# PCB_tp1.net
KiCad netlist of a schematic drawn in Altium Designer
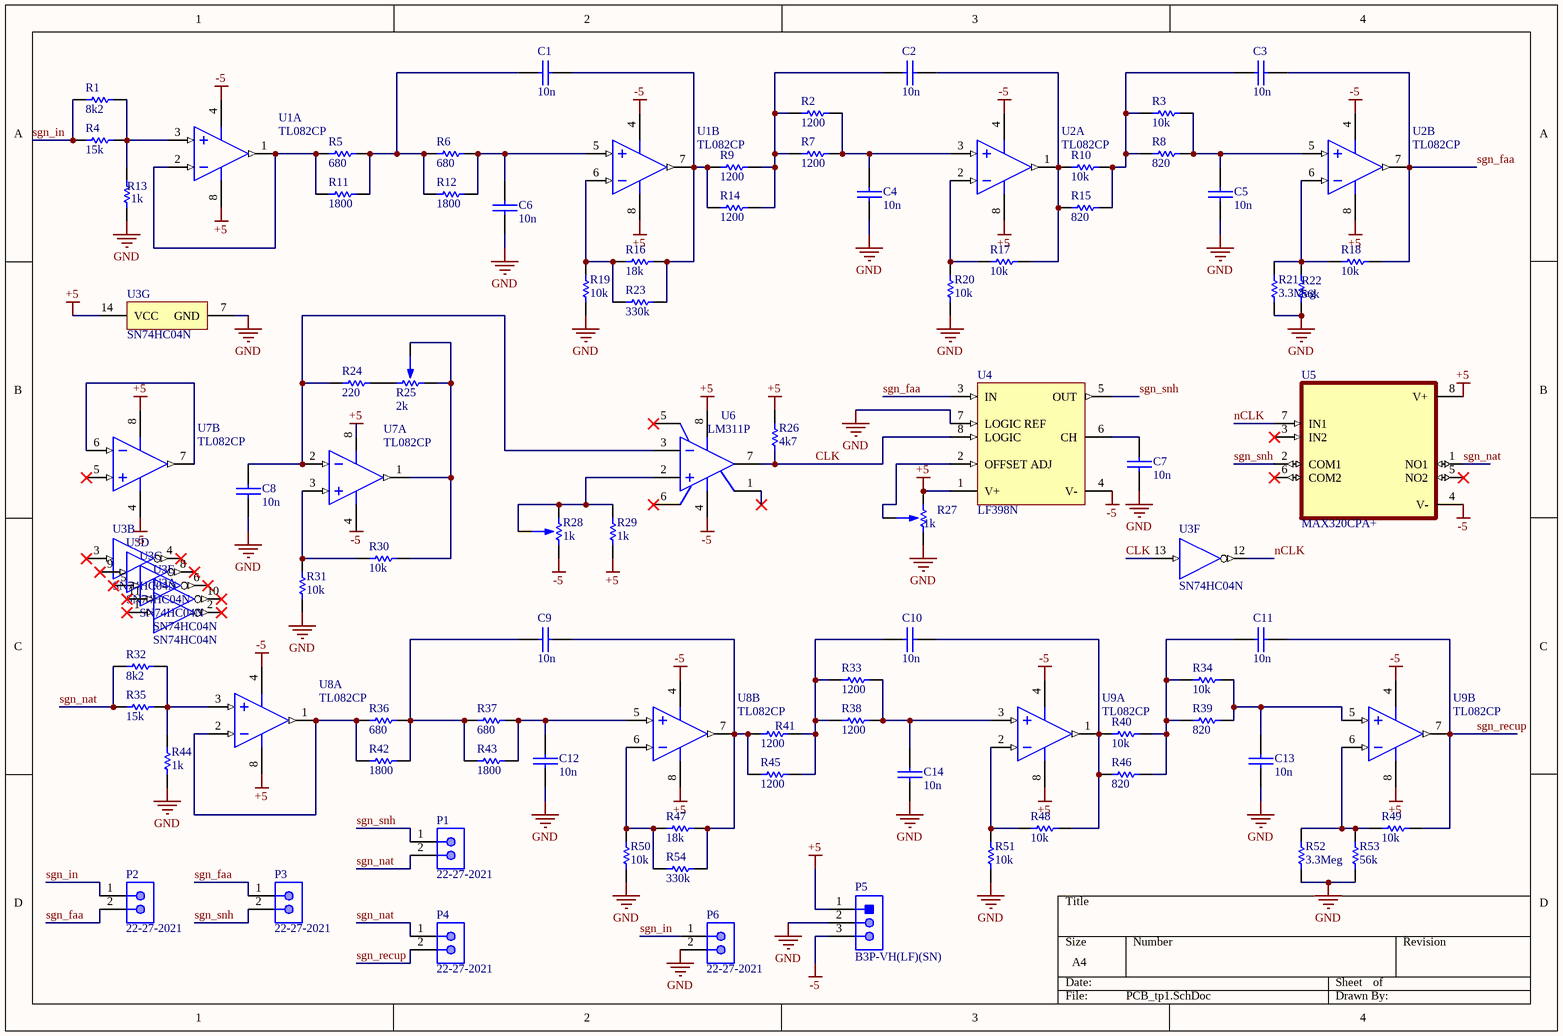
[diagram p0: PCB_tp1.SchDoc]

(export (version "E")
  (design (tool "Eeschema 10.0.6"))
  (components
    (comp (ref "C1") (value "10n") (footprint "CAP200") (libsource (lib "LIBEBAL") (part "CAP")))
    (comp (ref "C2") (value "10n") (footprint "CAP200") (libsource (lib "LIBEBAL") (part "CAP")))
    (comp (ref "C3") (value "10n") (footprint "CAP200") (libsource (lib "LIBEBAL") (part "CAP")))
    (comp (ref "C4") (value "10n") (footprint "CAP200") (libsource (lib "LIBEBAL") (part "CAP")))
    (comp (ref "C5") (value "10n") (footprint "CAP200") (libsource (lib "LIBEBAL") (part "CAP")))
    (comp (ref "C6") (value "10n") (footprint "CAP200") (libsource (lib "LIBEBAL") (part "CAP")))
    (comp (ref "C7") (value "10n") (footprint "CAP200") (libsource (lib "LIBEBAL") (part "CAP")))
    (comp (ref "C8") (value "10n") (footprint "CAP200") (libsource (lib "LIBEBAL") (part "CAP")))
    (comp (ref "C9") (value "10n") (footprint "CAP200") (libsource (lib "LIBEBAL") (part "CAP")))
    (comp (ref "C10") (value "10n") (footprint "CAP200") (libsource (lib "LIBEBAL") (part "CAP")))
    (comp (ref "C11") (value "10n") (footprint "CAP200") (libsource (lib "LIBEBAL") (part "CAP")))
    (comp (ref "C12") (value "10n") (footprint "CAP200") (libsource (lib "LIBEBAL") (part "CAP")))
    (comp (ref "C13") (value "10n") (footprint "CAP200") (libsource (lib "LIBEBAL") (part "CAP")))
    (comp (ref "C14") (value "10n") (footprint "CAP200") (libsource (lib "LIBEBAL") (part "CAP")))
    (comp (ref "P1")
      (value "22-27-2021")
      (footprint "MOLX-22-27-2021_V")
      (fields (field (name "MANUFACTURER") "Molex") (field (name "PARTNUMBER") "0022272021"))
      (libsource (lib "Altium Content Vault") (part "CN-1P-M-R2"))
    )
    (comp (ref "P2")
      (value "22-27-2021")
      (footprint "MOLX-22-27-2021_V")
      (fields (field (name "MANUFACTURER") "Molex") (field (name "PARTNUMBER") "0022272021"))
      (libsource (lib "Altium Content Vault") (part "CN-1P-M-R2"))
    )
    (comp (ref "P3")
      (value "22-27-2021")
      (footprint "MOLX-22-27-2021_V")
      (fields (field (name "MANUFACTURER") "Molex") (field (name "PARTNUMBER") "0022272021"))
      (libsource (lib "Altium Content Vault") (part "CN-1P-M-R2"))
    )
    (comp (ref "P4")
      (value "22-27-2021")
      (footprint "MOLX-22-27-2021_V")
      (fields (field (name "MANUFACTURER") "Molex") (field (name "PARTNUMBER") "0022272021"))
      (libsource (lib "Altium Content Vault") (part "CN-1P-M-R2"))
    )
    (comp (ref "P5")
      (value "B3P-VH(LF)(SN)")
      (footprint "JST-B3P-VH(LF)(SN)-3_V")
      (libsource (lib "Altium Content Vault") (part "CN-1P-M-R3"))
    )
    (comp (ref "P6")
      (value "22-27-2021")
      (footprint "MOLX-22-27-2021_V")
      (fields (field (name "MANUFACTURER") "Molex") (field (name "PARTNUMBER") "0022272021"))
      (libsource (lib "Altium Content Vault") (part "CN-1P-M-R2"))
    )
    (comp (ref "R1") (value "8k2") (footprint "RES400") (libsource (lib "LIBEBAL") (part "RES")))
    (comp (ref "R2") (value "1200") (footprint "RES400") (libsource (lib "LIBEBAL") (part "RES")))
    (comp (ref "R3") (value "10k") (footprint "RES400") (libsource (lib "LIBEBAL") (part "RES")))
    (comp (ref "R4") (value "15k") (footprint "RES400") (libsource (lib "LIBEBAL") (part "RES")))
    (comp (ref "R5") (value "680") (footprint "RES400") (libsource (lib "LIBEBAL") (part "RES")))
    (comp (ref "R6") (value "680") (footprint "RES400") (libsource (lib "LIBEBAL") (part "RES")))
    (comp (ref "R7") (value "1200") (footprint "RES400") (libsource (lib "LIBEBAL") (part "RES")))
    (comp (ref "R8") (value "820") (footprint "RES400") (libsource (lib "LIBEBAL") (part "RES")))
    (comp (ref "R9") (value "1200") (footprint "RES400") (libsource (lib "LIBEBAL") (part "RES")))
    (comp (ref "R10") (value "10k") (footprint "RES400") (libsource (lib "LIBEBAL") (part "RES")))
    (comp (ref "R11") (value "1800") (footprint "RES400") (libsource (lib "LIBEBAL") (part "RES")))
    (comp (ref "R12") (value "1800") (footprint "RES400") (libsource (lib "LIBEBAL") (part "RES")))
    (comp (ref "R13") (value "1k") (footprint "RES400") (libsource (lib "LIBEBAL") (part "RES")))
    (comp (ref "R14") (value "1200") (footprint "RES400") (libsource (lib "LIBEBAL") (part "RES")))
    (comp (ref "R15") (value "820") (footprint "RES400") (libsource (lib "LIBEBAL") (part "RES")))
    (comp (ref "R16") (value "18k") (footprint "RES400") (libsource (lib "LIBEBAL") (part "RES")))
    (comp (ref "R17") (value "10k") (footprint "RES400") (libsource (lib "LIBEBAL") (part "RES")))
    (comp (ref "R18") (value "10k") (footprint "RES400") (libsource (lib "LIBEBAL") (part "RES")))
    (comp (ref "R19") (value "10k") (footprint "RES400") (libsource (lib "LIBEBAL") (part "RES")))
    (comp (ref "R20") (value "10k") (footprint "RES400") (libsource (lib "LIBEBAL") (part "RES")))
    (comp (ref "R21") (value "3.3Meg") (footprint "RES400") (libsource (lib "LIBEBAL") (part "RES")))
    (comp (ref "R22") (value "56k") (footprint "RES400") (libsource (lib "LIBEBAL") (part "RES")))
    (comp (ref "R23") (value "330k") (footprint "RES400") (libsource (lib "LIBEBAL") (part "RES")))
    (comp (ref "R24") (value "220") (footprint "RES400") (libsource (lib "LIBEBAL") (part "RES")))
    (comp (ref "R25")
      (value "2k")
      (footprint "POTENCIOMETRO")
      (libsource (lib "LIBEBAL") (part "POTENCIOMETRO"))
    )
    (comp (ref "R26") (value "4k7") (footprint "RES400") (libsource (lib "LIBEBAL") (part "RES")))
    (comp (ref "R27") (value "1k") (footprint "PRESET H") (libsource (lib "LIBEBAL") (part "PRESET")))
    (comp (ref "R28")
      (value "1k")
      (footprint "POTENCIOMETRO")
      (libsource (lib "LIBEBAL") (part "POTENCIOMETRO"))
    )
    (comp (ref "R29") (value "1k") (footprint "RES400") (libsource (lib "LIBEBAL") (part "RES")))
    (comp (ref "R30") (value "10k") (footprint "RES400") (libsource (lib "LIBEBAL") (part "RES")))
    (comp (ref "R31") (value "10k") (footprint "RES400") (libsource (lib "LIBEBAL") (part "RES")))
    (comp (ref "R32") (value "8k2") (footprint "RES400") (libsource (lib "LIBEBAL") (part "RES")))
    (comp (ref "R33") (value "1200") (footprint "RES400") (libsource (lib "LIBEBAL") (part "RES")))
    (comp (ref "R34") (value "10k") (footprint "RES400") (libsource (lib "LIBEBAL") (part "RES")))
    (comp (ref "R35") (value "15k") (footprint "RES400") (libsource (lib "LIBEBAL") (part "RES")))
    (comp (ref "R36") (value "680") (footprint "RES400") (libsource (lib "LIBEBAL") (part "RES")))
    (comp (ref "R37") (value "680") (footprint "RES400") (libsource (lib "LIBEBAL") (part "RES")))
    (comp (ref "R38") (value "1200") (footprint "RES400") (libsource (lib "LIBEBAL") (part "RES")))
    (comp (ref "R39") (value "820") (footprint "RES400") (libsource (lib "LIBEBAL") (part "RES")))
    (comp (ref "R40") (value "10k") (footprint "RES400") (libsource (lib "LIBEBAL") (part "RES")))
    (comp (ref "R41") (value "1200") (footprint "RES400") (libsource (lib "LIBEBAL") (part "RES")))
    (comp (ref "R42") (value "1800") (footprint "RES400") (libsource (lib "LIBEBAL") (part "RES")))
    (comp (ref "R43") (value "1800") (footprint "RES400") (libsource (lib "LIBEBAL") (part "RES")))
    (comp (ref "R44") (value "1k") (footprint "RES400") (libsource (lib "LIBEBAL") (part "RES")))
    (comp (ref "R45") (value "1200") (footprint "RES400") (libsource (lib "LIBEBAL") (part "RES")))
    (comp (ref "R46") (value "820") (footprint "RES400") (libsource (lib "LIBEBAL") (part "RES")))
    (comp (ref "R47") (value "18k") (footprint "RES400") (libsource (lib "LIBEBAL") (part "RES")))
    (comp (ref "R48") (value "10k") (footprint "RES400") (libsource (lib "LIBEBAL") (part "RES")))
    (comp (ref "R49") (value "10k") (footprint "RES400") (libsource (lib "LIBEBAL") (part "RES")))
    (comp (ref "R50") (value "10k") (footprint "RES400") (libsource (lib "LIBEBAL") (part "RES")))
    (comp (ref "R51") (value "10k") (footprint "RES400") (libsource (lib "LIBEBAL") (part "RES")))
    (comp (ref "R52") (value "3.3Meg") (footprint "RES400") (libsource (lib "LIBEBAL") (part "RES")))
    (comp (ref "R53") (value "56k") (footprint "RES400") (libsource (lib "LIBEBAL") (part "RES")))
    (comp (ref "R54") (value "330k") (footprint "RES400") (libsource (lib "LIBEBAL") (part "RES")))
    (comp (ref "U1")
      (value "TL082CP")
      (footprint "P0008A")
      (description "JFET-Input Operational Amplifier, 7 to 36 V, 0 to 70 degC, 8-pin DIP (P8), Pb-Free (RoHS)")
      (fields (field (name "MANUFACTURER") "Texas Instruments"))
      (libsource (lib "Altium Content Vault") (part "TI-AMP-D6-2-8_D"))
    )
    (comp (ref "U2")
      (value "TL082CP")
      (footprint "P0008A")
      (description "JFET-Input Operational Amplifier, 7 to 36 V, 0 to 70 degC, 8-pin DIP (P8), Pb-Free (RoHS)")
      (fields (field (name "MANUFACTURER") "Texas Instruments"))
      (libsource (lib "Altium Content Vault") (part "TI-AMP-D6-2-8_D"))
    )
    (comp (ref "U3")
      (value "SN74HC04N")
      (footprint "N0014A")
      (description "Hex Inverters, N0014A, TUBE")
      (fields
        (field (name "MANUFACTURER") "Texas Instruments")
        (field (name "GENERIC PART NUMBER") "SN74HC04")
      )
      (libsource (lib "Altium Content Vault") (part "TI-CD_SNX4XXXXXX4X_19A-14"))
    )
    (comp (ref "U4")
      (value "LF398N")
      (footprint "N08E")
      (description "Monolithic Sample and Hold Circuits, 8-pin MDIP")
      (fields (field (name "MANUFACTURER") "National Semiconductor"))
      (libsource (lib "Altium Content Vault") (part "AMP-SHA-LFX98-8"))
    )
    (comp (ref "U5")
      (value "MAX320CPA+")
      (footprint "DIP794W47P254L991H457Q8")
      (description "Precision, Dual Supply, SPST, Analog CMOS Switches")
      (fields (field (name "MF") "Analog Devices"))
      (libsource (lib "MAX320CPA_") (part "MAX320CPA+"))
    )
    (comp (ref "U6")
      (value "LM311P")
      (footprint "FP-P0008A-MFG")
      (fields (field (name "TOLERANCE") "1%"))
      (libsource (lib "Altium Content Vault") (part "b2b1c66385073ed7f685b7e01cc60c1"))
    )
    (comp (ref "U7")
      (value "TL082CP")
      (footprint "P0008A")
      (description "JFET-Input Operational Amplifier, 7 to 36 V, 0 to 70 degC, 8-pin DIP (P8), Pb-Free (RoHS)")
      (fields (field (name "MANUFACTURER") "Texas Instruments"))
      (libsource (lib "Altium Content Vault") (part "TI-AMP-D6-2-8_D"))
    )
    (comp (ref "U8")
      (value "TL082CP")
      (footprint "P0008A")
      (description "JFET-Input Operational Amplifier, 7 to 36 V, 0 to 70 degC, 8-pin DIP (P8), Pb-Free (RoHS)")
      (fields (field (name "MANUFACTURER") "Texas Instruments"))
      (libsource (lib "Altium Content Vault") (part "TI-AMP-D6-2-8_D"))
    )
    (comp (ref "U9")
      (value "TL082CP")
      (footprint "P0008A")
      (description "JFET-Input Operational Amplifier, 7 to 36 V, 0 to 70 degC, 8-pin DIP (P8), Pb-Free (RoHS)")
      (fields (field (name "MANUFACTURER") "Texas Instruments"))
      (libsource (lib "Altium Content Vault") (part "TI-AMP-D6-2-8_D"))
    )
  )
  (nets
    (net (code "1") (name "+5") (class "Default")
      (node (ref "P5") (pin "1") (pinfunction "1_1") (pintype "passive"))
      (node (ref "R26") (pin "1") (pinfunction "1_1") (pintype "passive"))
      (node (ref "R27") (pin "3") (pinfunction "3_3") (pintype "passive"))
      (node (ref "R29") (pin "2") (pinfunction "2_2") (pintype "passive"))
      (node (ref "U1") (pin "8") (pinfunction "VCC+_8") (pintype "power_in"))
      (node (ref "U2") (pin "8") (pinfunction "VCC+_8") (pintype "power_in"))
      (node (ref "U3") (pin "14") (pinfunction "VCC_14") (pintype "power_in"))
      (node (ref "U4") (pin "1") (pinfunction "V+_1") (pintype "power_in"))
      (node (ref "U5") (pin "8") (pinfunction "V+_8") (pintype "power_in"))
      (node (ref "U6") (pin "8") (pinfunction "VCC+_8") (pintype "power_in"))
      (node (ref "U7") (pin "8") (pinfunction "VCC+_8") (pintype "power_in"))
      (node (ref "U8") (pin "8") (pinfunction "VCC+_8") (pintype "power_in"))
      (node (ref "U9") (pin "8") (pinfunction "VCC+_8") (pintype "power_in"))
    )
    (net (code "2") (name "-5") (class "Default")
      (node (ref "P5") (pin "3") (pinfunction "3_3") (pintype "passive"))
      (node (ref "R28") (pin "1") (pinfunction "1_1") (pintype "passive"))
      (node (ref "U1") (pin "4") (pinfunction "VCC-_4") (pintype "power_in"))
      (node (ref "U2") (pin "4") (pinfunction "VCC-_4") (pintype "power_in"))
      (node (ref "U4") (pin "4") (pinfunction "V-_4") (pintype "power_in"))
      (node (ref "U5") (pin "4") (pinfunction "V-_4") (pintype "power_in"))
      (node (ref "U6") (pin "4") (pinfunction "VCC-_4") (pintype "power_in"))
      (node (ref "U7") (pin "4") (pinfunction "VCC-_4") (pintype "power_in"))
      (node (ref "U8") (pin "4") (pinfunction "VCC-_4") (pintype "power_in"))
      (node (ref "U9") (pin "4") (pinfunction "VCC-_4") (pintype "power_in"))
    )
    (net (code "3") (name "/CLK") (class "Default")
      (node (ref "R26") (pin "2") (pinfunction "2_2") (pintype "passive"))
      (node (ref "U3") (pin "13") (pinfunction "6A_13") (pintype "input"))
      (node (ref "U4") (pin "8") (pinfunction "LOGIC_8") (pintype "input"))
      (node (ref "U6") (pin "7") (pinfunction "COL_OUT_7") (pintype "open_collector"))
    )
    (net (code "4") (name "/nCLK") (class "Default")
      (node (ref "U3") (pin "12") (pinfunction "~{6Y}_12") (pintype "output"))
      (node (ref "U5") (pin "7") (pinfunction "IN1_7") (pintype "input"))
    )
    (net (code "5") (name "/sgn_faa") (class "Default")
      (node (ref "C3") (pin "2") (pinfunction "2_2") (pintype "passive"))
      (node (ref "P2") (pin "2") (pinfunction "2_2") (pintype "passive"))
      (node (ref "P3") (pin "1") (pinfunction "1_1") (pintype "passive"))
      (node (ref "R18") (pin "2") (pinfunction "2_2") (pintype "passive"))
      (node (ref "U2") (pin "7") (pinfunction "OUT2_7") (pintype "output"))
      (node (ref "U4") (pin "3") (pinfunction "IN_3") (pintype "input"))
    )
    (net (code "6") (name "/sgn_in") (class "Default")
      (node (ref "P2") (pin "1") (pinfunction "1_1") (pintype "passive"))
      (node (ref "P6") (pin "1") (pinfunction "1_1") (pintype "passive"))
      (node (ref "R1") (pin "1") (pinfunction "1_1") (pintype "passive"))
      (node (ref "R4") (pin "1") (pinfunction "1_1") (pintype "passive"))
    )
    (net (code "7") (name "/sgn_nat") (class "Default")
      (node (ref "P1") (pin "2") (pinfunction "2_2") (pintype "passive"))
      (node (ref "P4") (pin "1") (pinfunction "1_1") (pintype "passive"))
      (node (ref "R32") (pin "1") (pinfunction "1_1") (pintype "passive"))
      (node (ref "R35") (pin "1") (pinfunction "1_1") (pintype "passive"))
      (node (ref "U5") (pin "1") (pinfunction "NO1_1") (pintype "bidirectional"))
    )
    (net (code "8") (name "/sgn_recup") (class "Default")
      (node (ref "C11") (pin "2") (pinfunction "2_2") (pintype "passive"))
      (node (ref "P4") (pin "2") (pinfunction "2_2") (pintype "passive"))
      (node (ref "R49") (pin "2") (pinfunction "2_2") (pintype "passive"))
      (node (ref "U9") (pin "7") (pinfunction "OUT2_7") (pintype "output"))
    )
    (net (code "9") (name "/sgn_snh") (class "Default")
      (node (ref "P1") (pin "1") (pinfunction "1_1") (pintype "passive"))
      (node (ref "P3") (pin "2") (pinfunction "2_2") (pintype "passive"))
      (node (ref "U4") (pin "5") (pinfunction "OUT_5") (pintype "output"))
      (node (ref "U5") (pin "2") (pinfunction "COM1_2") (pintype "bidirectional"))
    )
    (net (code "10") (name "GND") (class "Default")
      (node (ref "C12") (pin "2") (pinfunction "2_2") (pintype "passive"))
      (node (ref "C13") (pin "2") (pinfunction "2_2") (pintype "passive"))
      (node (ref "C14") (pin "1") (pinfunction "1_1") (pintype "passive"))
      (node (ref "C4") (pin "1") (pinfunction "1_1") (pintype "passive"))
      (node (ref "C5") (pin "2") (pinfunction "2_2") (pintype "passive"))
      (node (ref "C6") (pin "2") (pinfunction "2_2") (pintype "passive"))
      (node (ref "C7") (pin "2") (pinfunction "2_2") (pintype "passive"))
      (node (ref "C8") (pin "2") (pinfunction "2_2") (pintype "passive"))
      (node (ref "P5") (pin "2") (pinfunction "2_2") (pintype "passive"))
      (node (ref "P6") (pin "2") (pinfunction "2_2") (pintype "passive"))
      (node (ref "R13") (pin "1") (pinfunction "1_1") (pintype "passive"))
      (node (ref "R19") (pin "2") (pinfunction "2_2") (pintype "passive"))
      (node (ref "R20") (pin "1") (pinfunction "1_1") (pintype "passive"))
      (node (ref "R21") (pin "2") (pinfunction "2_2") (pintype "passive"))
      (node (ref "R22") (pin "2") (pinfunction "2_2") (pintype "passive"))
      (node (ref "R27") (pin "1") (pinfunction "1_1") (pintype "passive"))
      (node (ref "R31") (pin "1") (pinfunction "1_1") (pintype "passive"))
      (node (ref "R44") (pin "1") (pinfunction "1_1") (pintype "passive"))
      (node (ref "R50") (pin "2") (pinfunction "2_2") (pintype "passive"))
      (node (ref "R51") (pin "1") (pinfunction "1_1") (pintype "passive"))
      (node (ref "R52") (pin "2") (pinfunction "2_2") (pintype "passive"))
      (node (ref "R53") (pin "2") (pinfunction "2_2") (pintype "passive"))
      (node (ref "U3") (pin "7") (pinfunction "GND_7") (pintype "power_in"))
      (node (ref "U4") (pin "7") (pinfunction "LOGIC_REF_7") (pintype "input"))
    )
    (net (code "11") (name "Net-(C1-Pad1)") (class "Default")
      (node (ref "C1") (pin "1") (pinfunction "1_1") (pintype "passive"))
      (node (ref "R11") (pin "1") (pinfunction "1_1") (pintype "passive"))
      (node (ref "R12") (pin "2") (pinfunction "2_2") (pintype "passive"))
      (node (ref "R5") (pin "1") (pinfunction "1_1") (pintype "passive"))
      (node (ref "R6") (pin "2") (pinfunction "2_2") (pintype "passive"))
    )
    (net (code "12") (name "Net-(C2-Pad2)") (class "Default")
      (node (ref "C2") (pin "2") (pinfunction "2_2") (pintype "passive"))
      (node (ref "R14") (pin "2") (pinfunction "2_2") (pintype "passive"))
      (node (ref "R2") (pin "1") (pinfunction "1_1") (pintype "passive"))
      (node (ref "R7") (pin "1") (pinfunction "1_1") (pintype "passive"))
      (node (ref "R9") (pin "2") (pinfunction "2_2") (pintype "passive"))
    )
    (net (code "13") (name "Net-(C3-Pad1)") (class "Default")
      (node (ref "C3") (pin "1") (pinfunction "1_1") (pintype "passive"))
      (node (ref "R10") (pin "1") (pinfunction "1_1") (pintype "passive"))
      (node (ref "R15") (pin "1") (pinfunction "1_1") (pintype "passive"))
      (node (ref "R3") (pin "2") (pinfunction "2_2") (pintype "passive"))
      (node (ref "R8") (pin "2") (pinfunction "2_2") (pintype "passive"))
    )
    (net (code "14") (name "Net-(C9-Pad1)") (class "Default")
      (node (ref "C9") (pin "1") (pinfunction "1_1") (pintype "passive"))
      (node (ref "R36") (pin "1") (pinfunction "1_1") (pintype "passive"))
      (node (ref "R37") (pin "2") (pinfunction "2_2") (pintype "passive"))
      (node (ref "R42") (pin "1") (pinfunction "1_1") (pintype "passive"))
      (node (ref "R43") (pin "2") (pinfunction "2_2") (pintype "passive"))
    )
    (net (code "15") (name "Net-(C10-Pad2)") (class "Default")
      (node (ref "C10") (pin "2") (pinfunction "2_2") (pintype "passive"))
      (node (ref "R33") (pin "1") (pinfunction "1_1") (pintype "passive"))
      (node (ref "R38") (pin "1") (pinfunction "1_1") (pintype "passive"))
      (node (ref "R41") (pin "2") (pinfunction "2_2") (pintype "passive"))
      (node (ref "R45") (pin "2") (pinfunction "2_2") (pintype "passive"))
    )
    (net (code "16") (name "Net-(C11-Pad1)") (class "Default")
      (node (ref "C11") (pin "1") (pinfunction "1_1") (pintype "passive"))
      (node (ref "R34") (pin "2") (pinfunction "2_2") (pintype "passive"))
      (node (ref "R39") (pin "2") (pinfunction "2_2") (pintype "passive"))
      (node (ref "R40") (pin "1") (pinfunction "1_1") (pintype "passive"))
      (node (ref "R46") (pin "1") (pinfunction "1_1") (pintype "passive"))
    )
    (net (code "17") (name "Net-(R24-Pad1)") (class "Default")
      (node (ref "R24") (pin "1") (pinfunction "1_1") (pintype "passive"))
      (node (ref "R25") (pin "1") (pinfunction "1_1") (pintype "passive"))
    )
    (net (code "18") (name "Net-(U1A-IN1+)") (class "Default")
      (node (ref "R1") (pin "2") (pinfunction "2_2") (pintype "passive"))
      (node (ref "R13") (pin "2") (pinfunction "2_2") (pintype "passive"))
      (node (ref "R4") (pin "2") (pinfunction "2_2") (pintype "passive"))
      (node (ref "U1") (pin "3") (pinfunction "IN1+_3") (pintype "input"))
    )
    (net (code "19") (name "Net-(U1A-IN1-)") (class "Default")
      (node (ref "R11") (pin "2") (pinfunction "2_2") (pintype "passive"))
      (node (ref "R5") (pin "2") (pinfunction "2_2") (pintype "passive"))
      (node (ref "U1") (pin "1") (pinfunction "OUT1_1") (pintype "output"))
      (node (ref "U1") (pin "2") (pinfunction "IN1-_2") (pintype "input"))
    )
    (net (code "20") (name "Net-(U1B-IN2+)") (class "Default")
      (node (ref "C6") (pin "1") (pinfunction "1_1") (pintype "passive"))
      (node (ref "R12") (pin "1") (pinfunction "1_1") (pintype "passive"))
      (node (ref "R6") (pin "1") (pinfunction "1_1") (pintype "passive"))
      (node (ref "U1") (pin "5") (pinfunction "IN2+_5") (pintype "input"))
    )
    (net (code "21") (name "Net-(U1B-IN2-)") (class "Default")
      (node (ref "R16") (pin "2") (pinfunction "2_2") (pintype "passive"))
      (node (ref "R19") (pin "1") (pinfunction "1_1") (pintype "passive"))
      (node (ref "R23") (pin "2") (pinfunction "2_2") (pintype "passive"))
      (node (ref "U1") (pin "6") (pinfunction "IN2-_6") (pintype "input"))
    )
    (net (code "22") (name "Net-(U1B-OUT2)") (class "Default")
      (node (ref "C1") (pin "2") (pinfunction "2_2") (pintype "passive"))
      (node (ref "R14") (pin "1") (pinfunction "1_1") (pintype "passive"))
      (node (ref "R16") (pin "1") (pinfunction "1_1") (pintype "passive"))
      (node (ref "R23") (pin "1") (pinfunction "1_1") (pintype "passive"))
      (node (ref "R9") (pin "1") (pinfunction "1_1") (pintype "passive"))
      (node (ref "U1") (pin "7") (pinfunction "OUT2_7") (pintype "output"))
    )
    (net (code "23") (name "Net-(U2A-IN1+)") (class "Default")
      (node (ref "C4") (pin "2") (pinfunction "2_2") (pintype "passive"))
      (node (ref "R2") (pin "2") (pinfunction "2_2") (pintype "passive"))
      (node (ref "R7") (pin "2") (pinfunction "2_2") (pintype "passive"))
      (node (ref "U2") (pin "3") (pinfunction "IN1+_3") (pintype "input"))
    )
    (net (code "24") (name "Net-(U2A-IN1-)") (class "Default")
      (node (ref "R17") (pin "2") (pinfunction "2_2") (pintype "passive"))
      (node (ref "R20") (pin "2") (pinfunction "2_2") (pintype "passive"))
      (node (ref "U2") (pin "2") (pinfunction "IN1-_2") (pintype "input"))
    )
    (net (code "25") (name "Net-(U2A-OUT1)") (class "Default")
      (node (ref "C2") (pin "1") (pinfunction "1_1") (pintype "passive"))
      (node (ref "R10") (pin "2") (pinfunction "2_2") (pintype "passive"))
      (node (ref "R15") (pin "2") (pinfunction "2_2") (pintype "passive"))
      (node (ref "R17") (pin "1") (pinfunction "1_1") (pintype "passive"))
      (node (ref "U2") (pin "1") (pinfunction "OUT1_1") (pintype "output"))
    )
    (net (code "26") (name "Net-(U2B-IN2+)") (class "Default")
      (node (ref "C5") (pin "1") (pinfunction "1_1") (pintype "passive"))
      (node (ref "R3") (pin "1") (pinfunction "1_1") (pintype "passive"))
      (node (ref "R8") (pin "1") (pinfunction "1_1") (pintype "passive"))
      (node (ref "U2") (pin "5") (pinfunction "IN2+_5") (pintype "input"))
    )
    (net (code "27") (name "Net-(U2B-IN2-)") (class "Default")
      (node (ref "R18") (pin "1") (pinfunction "1_1") (pintype "passive"))
      (node (ref "R21") (pin "1") (pinfunction "1_1") (pintype "passive"))
      (node (ref "R22") (pin "1") (pinfunction "1_1") (pintype "passive"))
      (node (ref "U2") (pin "6") (pinfunction "IN2-_6") (pintype "input"))
    )
    (net (code "28") (name "Net-(U4-CH)") (class "Default")
      (node (ref "C7") (pin "1") (pinfunction "1_1") (pintype "passive"))
      (node (ref "U4") (pin "6") (pinfunction "CH_6") (pintype "passive"))
    )
    (net (code "29") (name "Net-(U4-OFFSET_ADJ)") (class "Default")
      (node (ref "R27") (pin "2") (pinfunction "2_2") (pintype "passive"))
      (node (ref "U4") (pin "2") (pinfunction "OFFSET_ADJ_2") (pintype "input"))
    )
    (net (code "30") (name "Net-(U6-IN+)") (class "Default")
      (node (ref "R28") (pin "2") (pinfunction "2_2") (pintype "passive"))
      (node (ref "R28") (pin "3") (pinfunction "3_3") (pintype "passive"))
      (node (ref "R29") (pin "1") (pinfunction "1_1") (pintype "passive"))
      (node (ref "U6") (pin "2") (pinfunction "IN+_2") (pintype "tri_state"))
    )
    (net (code "31") (name "Net-(U6-IN-)") (class "Default")
      (node (ref "C8") (pin "1") (pinfunction "1_1") (pintype "passive"))
      (node (ref "R24") (pin "2") (pinfunction "2_2") (pintype "passive"))
      (node (ref "U6") (pin "3") (pinfunction "IN-_3") (pintype "tri_state"))
      (node (ref "U7") (pin "2") (pinfunction "IN1-_2") (pintype "input"))
    )
    (net (code "32") (name "Net-(U7A-IN1+)") (class "Default")
      (node (ref "R30") (pin "1") (pinfunction "1_1") (pintype "passive"))
      (node (ref "R31") (pin "2") (pinfunction "2_2") (pintype "passive"))
      (node (ref "U7") (pin "3") (pinfunction "IN1+_3") (pintype "input"))
    )
    (net (code "33") (name "Net-(U7A-OUT1)") (class "Default")
      (node (ref "R25") (pin "2") (pinfunction "2_2") (pintype "passive"))
      (node (ref "R25") (pin "3") (pinfunction "3_3") (pintype "passive"))
      (node (ref "R30") (pin "2") (pinfunction "2_2") (pintype "passive"))
      (node (ref "U7") (pin "1") (pinfunction "OUT1_1") (pintype "output"))
    )
    (net (code "34") (name "Net-(U7B-IN2-)") (class "Default")
      (node (ref "U7") (pin "6") (pinfunction "IN2-_6") (pintype "input"))
      (node (ref "U7") (pin "7") (pinfunction "OUT2_7") (pintype "output"))
    )
    (net (code "35") (name "Net-(U8A-IN1+)") (class "Default")
      (node (ref "R32") (pin "2") (pinfunction "2_2") (pintype "passive"))
      (node (ref "R35") (pin "2") (pinfunction "2_2") (pintype "passive"))
      (node (ref "R44") (pin "2") (pinfunction "2_2") (pintype "passive"))
      (node (ref "U8") (pin "3") (pinfunction "IN1+_3") (pintype "input"))
    )
    (net (code "36") (name "Net-(U8A-IN1-)") (class "Default")
      (node (ref "R36") (pin "2") (pinfunction "2_2") (pintype "passive"))
      (node (ref "R42") (pin "2") (pinfunction "2_2") (pintype "passive"))
      (node (ref "U8") (pin "1") (pinfunction "OUT1_1") (pintype "output"))
      (node (ref "U8") (pin "2") (pinfunction "IN1-_2") (pintype "input"))
    )
    (net (code "37") (name "Net-(U8B-IN2+)") (class "Default")
      (node (ref "C12") (pin "1") (pinfunction "1_1") (pintype "passive"))
      (node (ref "R37") (pin "1") (pinfunction "1_1") (pintype "passive"))
      (node (ref "R43") (pin "1") (pinfunction "1_1") (pintype "passive"))
      (node (ref "U8") (pin "5") (pinfunction "IN2+_5") (pintype "input"))
    )
    (net (code "38") (name "Net-(U8B-IN2-)") (class "Default")
      (node (ref "R47") (pin "1") (pinfunction "1_1") (pintype "passive"))
      (node (ref "R50") (pin "1") (pinfunction "1_1") (pintype "passive"))
      (node (ref "R54") (pin "1") (pinfunction "1_1") (pintype "passive"))
      (node (ref "U8") (pin "6") (pinfunction "IN2-_6") (pintype "input"))
    )
    (net (code "39") (name "Net-(U8B-OUT2)") (class "Default")
      (node (ref "C9") (pin "2") (pinfunction "2_2") (pintype "passive"))
      (node (ref "R41") (pin "1") (pinfunction "1_1") (pintype "passive"))
      (node (ref "R45") (pin "1") (pinfunction "1_1") (pintype "passive"))
      (node (ref "R47") (pin "2") (pinfunction "2_2") (pintype "passive"))
      (node (ref "R54") (pin "2") (pinfunction "2_2") (pintype "passive"))
      (node (ref "U8") (pin "7") (pinfunction "OUT2_7") (pintype "output"))
    )
    (net (code "40") (name "Net-(U9A-IN1+)") (class "Default")
      (node (ref "C14") (pin "2") (pinfunction "2_2") (pintype "passive"))
      (node (ref "R33") (pin "2") (pinfunction "2_2") (pintype "passive"))
      (node (ref "R38") (pin "2") (pinfunction "2_2") (pintype "passive"))
      (node (ref "U9") (pin "3") (pinfunction "IN1+_3") (pintype "input"))
    )
    (net (code "41") (name "Net-(U9A-IN1-)") (class "Default")
      (node (ref "R48") (pin "2") (pinfunction "2_2") (pintype "passive"))
      (node (ref "R51") (pin "2") (pinfunction "2_2") (pintype "passive"))
      (node (ref "U9") (pin "2") (pinfunction "IN1-_2") (pintype "input"))
    )
    (net (code "42") (name "Net-(U9A-OUT1)") (class "Default")
      (node (ref "C10") (pin "1") (pinfunction "1_1") (pintype "passive"))
      (node (ref "R40") (pin "2") (pinfunction "2_2") (pintype "passive"))
      (node (ref "R46") (pin "2") (pinfunction "2_2") (pintype "passive"))
      (node (ref "R48") (pin "1") (pinfunction "1_1") (pintype "passive"))
      (node (ref "U9") (pin "1") (pinfunction "OUT1_1") (pintype "output"))
    )
    (net (code "43") (name "Net-(U9B-IN2+)") (class "Default")
      (node (ref "C13") (pin "1") (pinfunction "1_1") (pintype "passive"))
      (node (ref "R34") (pin "1") (pinfunction "1_1") (pintype "passive"))
      (node (ref "R39") (pin "1") (pinfunction "1_1") (pintype "passive"))
      (node (ref "U9") (pin "5") (pinfunction "IN2+_5") (pintype "input"))
    )
    (net (code "44") (name "Net-(U9B-IN2-)") (class "Default")
      (node (ref "R49") (pin "1") (pinfunction "1_1") (pintype "passive"))
      (node (ref "R52") (pin "1") (pinfunction "1_1") (pintype "passive"))
      (node (ref "R53") (pin "1") (pinfunction "1_1") (pintype "passive"))
      (node (ref "U9") (pin "6") (pinfunction "IN2-_6") (pintype "input"))
    )
    (net (code "45") (name "unconnected-(U3A-1A-Pad1)") (class "Default")
      (node (ref "U3") (pin "1") (pinfunction "1A_1") (pintype "input+no_connect"))
    )
    (net (code "46") (name "unconnected-(U3A-~{1Y}-Pad2)") (class "Default")
      (node (ref "U3") (pin "2") (pinfunction "~{1Y}_2") (pintype "output+no_connect"))
    )
    (net (code "47") (name "unconnected-(U3B-2A-Pad3)") (class "Default")
      (node (ref "U3") (pin "3") (pinfunction "2A_3") (pintype "input+no_connect"))
    )
    (net (code "48") (name "unconnected-(U3B-~{2Y}-Pad4)") (class "Default")
      (node (ref "U3") (pin "4") (pinfunction "~{2Y}_4") (pintype "output+no_connect"))
    )
    (net (code "49") (name "unconnected-(U3C-3A-Pad5)") (class "Default")
      (node (ref "U3") (pin "5") (pinfunction "3A_5") (pintype "input+no_connect"))
    )
    (net (code "50") (name "unconnected-(U3C-~{3Y}-Pad6)") (class "Default")
      (node (ref "U3") (pin "6") (pinfunction "~{3Y}_6") (pintype "output+no_connect"))
    )
    (net (code "51") (name "unconnected-(U3D-4A-Pad9)") (class "Default")
      (node (ref "U3") (pin "9") (pinfunction "4A_9") (pintype "input+no_connect"))
    )
    (net (code "52") (name "unconnected-(U3D-~{4Y}-Pad8)") (class "Default")
      (node (ref "U3") (pin "8") (pinfunction "~{4Y}_8") (pintype "output+no_connect"))
    )
    (net (code "53") (name "unconnected-(U3E-5A-Pad11)") (class "Default")
      (node (ref "U3") (pin "11") (pinfunction "5A_11") (pintype "input+no_connect"))
    )
    (net (code "54") (name "unconnected-(U3E-~{5Y}-Pad10)") (class "Default")
      (node (ref "U3") (pin "10") (pinfunction "~{5Y}_10") (pintype "output+no_connect"))
    )
    (net (code "55") (name "unconnected-(U5-COM2-Pad6)") (class "Default")
      (node (ref "U5") (pin "6") (pinfunction "COM2_6") (pintype "bidirectional+no_connect"))
    )
    (net (code "56") (name "unconnected-(U5-IN2-Pad3)") (class "Default")
      (node (ref "U5") (pin "3") (pinfunction "IN2_3") (pintype "input+no_connect"))
    )
    (net (code "57") (name "unconnected-(U5-NO2-Pad5)") (class "Default")
      (node (ref "U5") (pin "5") (pinfunction "NO2_5") (pintype "bidirectional+no_connect"))
    )
    (net (code "58") (name "unconnected-(U6-BALANCE-Pad5)") (class "Default")
      (node (ref "U6") (pin "5") (pinfunction "BALANCE_5") (pintype "passive+no_connect"))
    )
    (net (code "59") (name "unconnected-(U6-BAL{slash}STRB-Pad6)") (class "Default")
      (node (ref "U6") (pin "6") (pinfunction "BAL/STRB_6") (pintype "passive+no_connect"))
    )
    (net (code "60") (name "unconnected-(U6-EMIT_OUT-Pad1)") (class "Default")
      (node (ref "U6") (pin "1") (pinfunction "EMIT_OUT_1") (pintype "open_emitter+no_connect"))
    )
    (net (code "61") (name "unconnected-(U7A-VCC--Pad4)") (class "Default")
      (node (ref "U7") (pin "4") (pinfunction "VCC-_4") (pintype "power_in"))
    )
    (net (code "62") (name "unconnected-(U7B-IN2+-Pad5)") (class "Default")
      (node (ref "U7") (pin "5") (pinfunction "IN2+_5") (pintype "input+no_connect"))
    )
  )
)
